# sound_amp.net
KiCad netlist of a schematic drawn in EAGLE
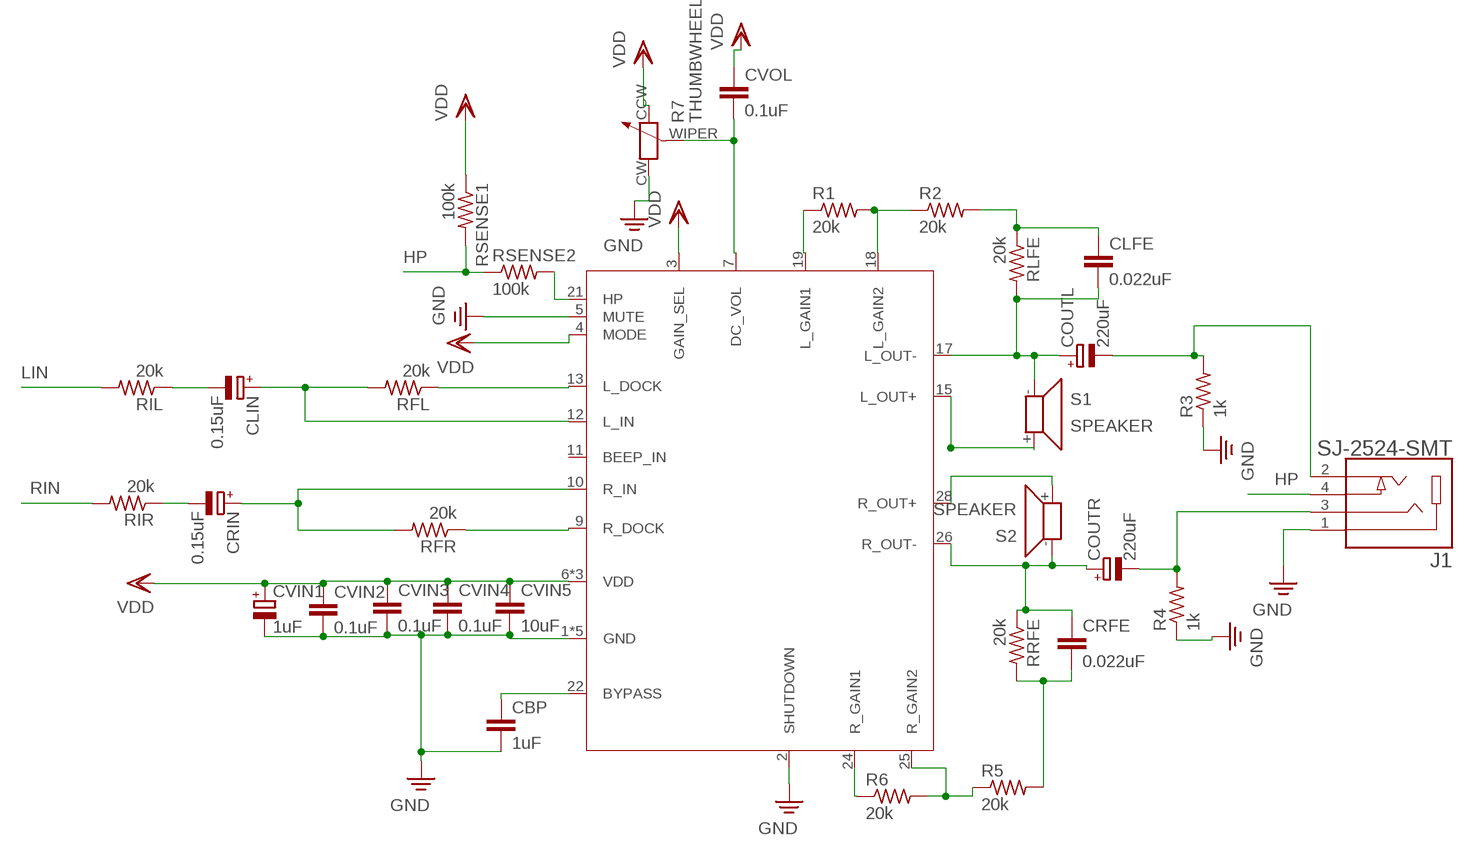
[diagram p0: schematic, sheet 1]

(export (version "E")
  (design (tool "Eeschema 10.0.6"))
  (components
    (comp (ref "CBP")
      (value "1uF")
      (footprint "eagle-import:C0603")
      (libsource (lib "eagle-import") (part "C-EUC0603"))
    )
    (comp (ref "CLFE")
      (value "0.022uF")
      (footprint "eagle-import:C0603")
      (libsource (lib "eagle-import") (part "C-EUC0603"))
    )
    (comp (ref "CLIN")
      (value "0.15uF")
      (footprint "eagle-import:B45181A")
      (libsource (lib "eagle-import") (part "CPOL-EUB45181A"))
    )
    (comp (ref "COUTL")
      (value "220uF")
      (footprint "eagle-import:B45181A")
      (libsource (lib "eagle-import") (part "CPOL-EUB45181A"))
    )
    (comp (ref "COUTR")
      (value "220uF")
      (footprint "eagle-import:B45181A")
      (libsource (lib "eagle-import") (part "CPOL-EUB45181A"))
    )
    (comp (ref "CRFE")
      (value "0.022uF")
      (footprint "eagle-import:C0603")
      (libsource (lib "eagle-import") (part "C-EUC0603"))
    )
    (comp (ref "CRIN")
      (value "0.15uF")
      (footprint "eagle-import:B45181A")
      (libsource (lib "eagle-import") (part "CPOL-EUB45181A"))
    )
    (comp (ref "CVIN1")
      (value "1uF")
      (footprint "eagle-import:B45181A")
      (libsource (lib "eagle-import") (part "CPOL-EUB45181A"))
    )
    (comp (ref "CVIN2")
      (value "0.1uF")
      (footprint "eagle-import:C0603")
      (libsource (lib "eagle-import") (part "C-EUC0603"))
    )
    (comp (ref "CVIN3")
      (value "0.1uF")
      (footprint "eagle-import:C0603")
      (libsource (lib "eagle-import") (part "C-EUC0603"))
    )
    (comp (ref "CVIN4")
      (value "0.1uF")
      (footprint "eagle-import:C0603")
      (libsource (lib "eagle-import") (part "C-EUC0603"))
    )
    (comp (ref "CVIN5")
      (value "10uF")
      (footprint "eagle-import:C0603")
      (libsource (lib "eagle-import") (part "C-EUC0603"))
    )
    (comp (ref "CVOL")
      (value "0.1uF")
      (footprint "eagle-import:C0603")
      (libsource (lib "eagle-import") (part "C-EUC0603"))
    )
    (comp (ref "J1")
      (value "SJ-2524-SMT")
      (footprint "eagle-import:CUI_SJ-2524-SMT")
      (fields (field (name "MF") "CUI Inc"))
      (libsource (lib "eagle-import") (part "SJ-2524-SMT"))
    )
    (comp (ref "R1")
      (value "20k")
      (footprint "eagle-import:R0603")
      (libsource (lib "eagle-import") (part "R-US_R0603"))
    )
    (comp (ref "R2")
      (value "20k")
      (footprint "eagle-import:R0603")
      (libsource (lib "eagle-import") (part "R-US_R0603"))
    )
    (comp (ref "R3")
      (value "1k")
      (footprint "eagle-import:R0603")
      (libsource (lib "eagle-import") (part "R-US_R0603"))
    )
    (comp (ref "R4")
      (value "1k")
      (footprint "eagle-import:R0603")
      (libsource (lib "eagle-import") (part "R-US_R0603"))
    )
    (comp (ref "R5")
      (value "20k")
      (footprint "eagle-import:R0603")
      (libsource (lib "eagle-import") (part "R-US_R0603"))
    )
    (comp (ref "R6")
      (value "20k")
      (footprint "eagle-import:R0603")
      (libsource (lib "eagle-import") (part "R-US_R0603"))
    )
    (comp (ref "R7")
      (value "THUMBWHEEL")
      (footprint "eagle-import:THUMBWHEEL")
      (libsource (lib "eagle-import") (part "THUMBWHEEL"))
    )
    (comp (ref "RFL")
      (value "20k")
      (footprint "eagle-import:R0603")
      (libsource (lib "eagle-import") (part "R-US_R0603"))
    )
    (comp (ref "RFR")
      (value "20k")
      (footprint "eagle-import:R0603")
      (libsource (lib "eagle-import") (part "R-US_R0603"))
    )
    (comp (ref "RIL")
      (value "20k")
      (footprint "eagle-import:R0603")
      (libsource (lib "eagle-import") (part "R-US_R0603"))
    )
    (comp (ref "RIR")
      (value "20k")
      (footprint "eagle-import:R0603")
      (libsource (lib "eagle-import") (part "R-US_R0603"))
    )
    (comp (ref "RLFE")
      (value "20k")
      (footprint "eagle-import:R0603")
      (libsource (lib "eagle-import") (part "R-US_R0603"))
    )
    (comp (ref "RRFE")
      (value "20k")
      (footprint "eagle-import:R0603")
      (libsource (lib "eagle-import") (part "R-US_R0603"))
    )
    (comp (ref "RSENSE1")
      (value "100k")
      (footprint "eagle-import:R0603")
      (libsource (lib "eagle-import") (part "R-US_R0603"))
    )
    (comp (ref "RSENSE2")
      (value "100k")
      (footprint "eagle-import:R0603")
      (libsource (lib "eagle-import") (part "R-US_R0603"))
    )
    (comp (ref "S1")
      (value "SPEAKER")
      (footprint "eagle-import:SIGNALOUT")
      (libsource (lib "eagle-import") (part "SPEAKER"))
    )
    (comp (ref "S2")
      (value "SPEAKER")
      (footprint "eagle-import:SIGNALOUT")
      (libsource (lib "eagle-import") (part "SPEAKER"))
    )
    (comp (ref "U1")
      (value "LM4835")
      (footprint "eagle-import:TSSOP-28")
      (libsource (lib "eagle-import") (part "LM4835"))
    )
  )
  (nets
    (net (code "1") (name "/HP") (class "Default")
      (node (ref "J1") (pin "4") (pinfunction "4_4") (pintype "passive"))
      (node (ref "RSENSE1") (pin "2") (pinfunction "2_2") (pintype "passive"))
      (node (ref "RSENSE2") (pin "1") (pinfunction "1_1") (pintype "passive"))
    )
    (net (code "2") (name "/LIN") (class "Default")
      (node (ref "RIL") (pin "2") (pinfunction "2_2") (pintype "passive"))
    )
    (net (code "3") (name "/RIN") (class "Default")
      (node (ref "RIR") (pin "2") (pinfunction "2_2") (pintype "passive"))
    )
    (net (code "4") (name "GND") (class "Default")
      (node (ref "CBP") (pin "2") (pinfunction "2_2") (pintype "passive"))
      (node (ref "CVIN1") (pin "-") (pinfunction "-_-") (pintype "passive"))
      (node (ref "CVIN2") (pin "2") (pinfunction "2_2") (pintype "passive"))
      (node (ref "CVIN3") (pin "2") (pinfunction "2_2") (pintype "passive"))
      (node (ref "CVIN4") (pin "2") (pinfunction "2_2") (pintype "passive"))
      (node (ref "CVIN5") (pin "2") (pinfunction "2_2") (pintype "passive"))
      (node (ref "J1") (pin "1") (pinfunction "1_1") (pintype "passive"))
      (node (ref "R3") (pin "1") (pinfunction "1_1") (pintype "passive"))
      (node (ref "R4") (pin "1") (pinfunction "1_1") (pintype "passive"))
      (node (ref "R7") (pin "CW") (pinfunction "CW_CW") (pintype "passive"))
      (node (ref "U1") (pin "1") (pinfunction "GND_1") (pintype "bidirectional"))
      (node (ref "U1") (pin "14") (pinfunction "GND_14") (pintype "bidirectional"))
      (node (ref "U1") (pin "2") (pinfunction "SHUTDOWN_2") (pintype "bidirectional"))
      (node (ref "U1") (pin "20") (pinfunction "GND_20") (pintype "bidirectional"))
      (node (ref "U1") (pin "23") (pinfunction "GND_23") (pintype "bidirectional"))
      (node (ref "U1") (pin "5") (pinfunction "MUTE_5") (pintype "bidirectional"))
      (node (ref "U1") (pin "8") (pinfunction "GND_8") (pintype "bidirectional"))
    )
    (net (code "5") (name "Net-(CLFE-Pad1)") (class "Default")
      (node (ref "CLFE") (pin "1") (pinfunction "1_1") (pintype "passive"))
      (node (ref "R2") (pin "2") (pinfunction "2_2") (pintype "passive"))
      (node (ref "RLFE") (pin "1") (pinfunction "1_1") (pintype "passive"))
    )
    (net (code "6") (name "Net-(CLIN-Pad-)") (class "Default")
      (node (ref "CLIN") (pin "-") (pinfunction "-_-") (pintype "passive"))
      (node (ref "RIL") (pin "1") (pinfunction "1_1") (pintype "passive"))
    )
    (net (code "7") (name "Net-(COUTL-Pad-)") (class "Default")
      (node (ref "COUTL") (pin "-") (pinfunction "-_-") (pintype "passive"))
      (node (ref "J1") (pin "2") (pinfunction "2_2") (pintype "passive"))
      (node (ref "R3") (pin "2") (pinfunction "2_2") (pintype "passive"))
    )
    (net (code "8") (name "Net-(COUTR-Pad-)") (class "Default")
      (node (ref "COUTR") (pin "-") (pinfunction "-_-") (pintype "passive"))
      (node (ref "J1") (pin "3") (pinfunction "3_3") (pintype "passive"))
      (node (ref "R4") (pin "2") (pinfunction "2_2") (pintype "passive"))
    )
    (net (code "9") (name "Net-(CRFE-Pad2)") (class "Default")
      (node (ref "CRFE") (pin "2") (pinfunction "2_2") (pintype "passive"))
      (node (ref "R5") (pin "2") (pinfunction "2_2") (pintype "passive"))
      (node (ref "RRFE") (pin "2") (pinfunction "2_2") (pintype "passive"))
    )
    (net (code "10") (name "Net-(CRIN-Pad-)") (class "Default")
      (node (ref "CRIN") (pin "-") (pinfunction "-_-") (pintype "passive"))
      (node (ref "RIR") (pin "1") (pinfunction "1_1") (pintype "passive"))
    )
    (net (code "11") (name "Net-(U1-BYPASS)") (class "Default")
      (node (ref "CBP") (pin "1") (pinfunction "1_1") (pintype "passive"))
      (node (ref "U1") (pin "22") (pinfunction "BYPASS_22") (pintype "bidirectional"))
    )
    (net (code "12") (name "Net-(U1-DC_VOL)") (class "Default")
      (node (ref "CVOL") (pin "2") (pinfunction "2_2") (pintype "passive"))
      (node (ref "R7") (pin "WIPER") (pinfunction "WIPER_WIPER") (pintype "passive"))
      (node (ref "U1") (pin "7") (pinfunction "DC_VOL_7") (pintype "bidirectional"))
    )
    (net (code "13") (name "Net-(U1-HP)") (class "Default")
      (node (ref "RSENSE2") (pin "2") (pinfunction "2_2") (pintype "passive"))
      (node (ref "U1") (pin "21") (pinfunction "HP_21") (pintype "bidirectional"))
    )
    (net (code "14") (name "Net-(U1-L_DOCK)") (class "Default")
      (node (ref "RFL") (pin "1") (pinfunction "1_1") (pintype "passive"))
      (node (ref "U1") (pin "13") (pinfunction "L_DOCK_13") (pintype "bidirectional"))
    )
    (net (code "15") (name "Net-(U1-L_GAIN1)") (class "Default")
      (node (ref "R1") (pin "1") (pinfunction "1_1") (pintype "passive"))
      (node (ref "U1") (pin "19") (pinfunction "L_GAIN1_19") (pintype "bidirectional"))
    )
    (net (code "16") (name "Net-(U1-L_GAIN2)") (class "Default")
      (node (ref "R1") (pin "2") (pinfunction "2_2") (pintype "passive"))
      (node (ref "R2") (pin "1") (pinfunction "1_1") (pintype "passive"))
      (node (ref "U1") (pin "18") (pinfunction "L_GAIN2_18") (pintype "bidirectional"))
    )
    (net (code "17") (name "Net-(U1-L_IN)") (class "Default")
      (node (ref "CLIN") (pin "+") (pinfunction "+_+") (pintype "passive"))
      (node (ref "RFL") (pin "2") (pinfunction "2_2") (pintype "passive"))
      (node (ref "U1") (pin "12") (pinfunction "L_IN_12") (pintype "bidirectional"))
    )
    (net (code "18") (name "Net-(U1-L_OUT+)") (class "Default")
      (node (ref "S1") (pin "+") (pinfunction "+_+") (pintype "passive"))
      (node (ref "U1") (pin "15") (pinfunction "L_OUT+_15") (pintype "bidirectional"))
    )
    (net (code "19") (name "Net-(U1-L_OUT-)") (class "Default")
      (node (ref "CLFE") (pin "2") (pinfunction "2_2") (pintype "passive"))
      (node (ref "COUTL") (pin "+") (pinfunction "+_+") (pintype "passive"))
      (node (ref "RLFE") (pin "2") (pinfunction "2_2") (pintype "passive"))
      (node (ref "S1") (pin "-") (pinfunction "-_-") (pintype "passive"))
      (node (ref "U1") (pin "17") (pinfunction "L_OUT-_17") (pintype "bidirectional"))
    )
    (net (code "20") (name "Net-(U1-R_DOCK)") (class "Default")
      (node (ref "RFR") (pin "1") (pinfunction "1_1") (pintype "passive"))
      (node (ref "U1") (pin "9") (pinfunction "R_DOCK_9") (pintype "bidirectional"))
    )
    (net (code "21") (name "Net-(U1-R_GAIN1)") (class "Default")
      (node (ref "R6") (pin "1") (pinfunction "1_1") (pintype "passive"))
      (node (ref "U1") (pin "24") (pinfunction "R_GAIN1_24") (pintype "bidirectional"))
    )
    (net (code "22") (name "Net-(U1-R_GAIN2)") (class "Default")
      (node (ref "R5") (pin "1") (pinfunction "1_1") (pintype "passive"))
      (node (ref "R6") (pin "2") (pinfunction "2_2") (pintype "passive"))
      (node (ref "U1") (pin "25") (pinfunction "R_GAIN2_25") (pintype "bidirectional"))
    )
    (net (code "23") (name "Net-(U1-R_IN)") (class "Default")
      (node (ref "CRIN") (pin "+") (pinfunction "+_+") (pintype "passive"))
      (node (ref "RFR") (pin "2") (pinfunction "2_2") (pintype "passive"))
      (node (ref "U1") (pin "10") (pinfunction "R_IN_10") (pintype "bidirectional"))
    )
    (net (code "24") (name "Net-(U1-R_OUT+)") (class "Default")
      (node (ref "S2") (pin "+") (pinfunction "+_+") (pintype "passive"))
      (node (ref "U1") (pin "28") (pinfunction "R_OUT+_28") (pintype "bidirectional"))
    )
    (net (code "25") (name "Net-(U1-R_OUT-)") (class "Default")
      (node (ref "COUTR") (pin "+") (pinfunction "+_+") (pintype "passive"))
      (node (ref "CRFE") (pin "1") (pinfunction "1_1") (pintype "passive"))
      (node (ref "RRFE") (pin "1") (pinfunction "1_1") (pintype "passive"))
      (node (ref "S2") (pin "-") (pinfunction "-_-") (pintype "passive"))
      (node (ref "U1") (pin "26") (pinfunction "R_OUT-_26") (pintype "bidirectional"))
    )
    (net (code "26") (name "VDD") (class "Default")
      (node (ref "CVIN1") (pin "+") (pinfunction "+_+") (pintype "passive"))
      (node (ref "CVIN2") (pin "1") (pinfunction "1_1") (pintype "passive"))
      (node (ref "CVIN3") (pin "1") (pinfunction "1_1") (pintype "passive"))
      (node (ref "CVIN4") (pin "1") (pinfunction "1_1") (pintype "passive"))
      (node (ref "CVIN5") (pin "1") (pinfunction "1_1") (pintype "passive"))
      (node (ref "CVOL") (pin "1") (pinfunction "1_1") (pintype "passive"))
      (node (ref "R7") (pin "CCW") (pinfunction "CCW_CCW") (pintype "passive"))
      (node (ref "RSENSE1") (pin "1") (pinfunction "1_1") (pintype "passive"))
      (node (ref "U1") (pin "16") (pinfunction "VDD_16") (pintype "bidirectional"))
      (node (ref "U1") (pin "27") (pinfunction "VDD_27") (pintype "bidirectional"))
      (node (ref "U1") (pin "3") (pinfunction "GAIN_SEL_3") (pintype "bidirectional"))
      (node (ref "U1") (pin "4") (pinfunction "MODE_4") (pintype "bidirectional"))
      (node (ref "U1") (pin "6") (pinfunction "VDD_6") (pintype "bidirectional"))
    )
    (net (code "27") (name "unconnected-(U1-BEEP_IN-Pad11)") (class "Default")
      (node (ref "U1") (pin "11") (pinfunction "BEEP_IN_11") (pintype "bidirectional"))
    )
  )
)
